# Cruzada_GPS_2015_rev1.net
KiCad netlist of a schematic drawn in EAGLE
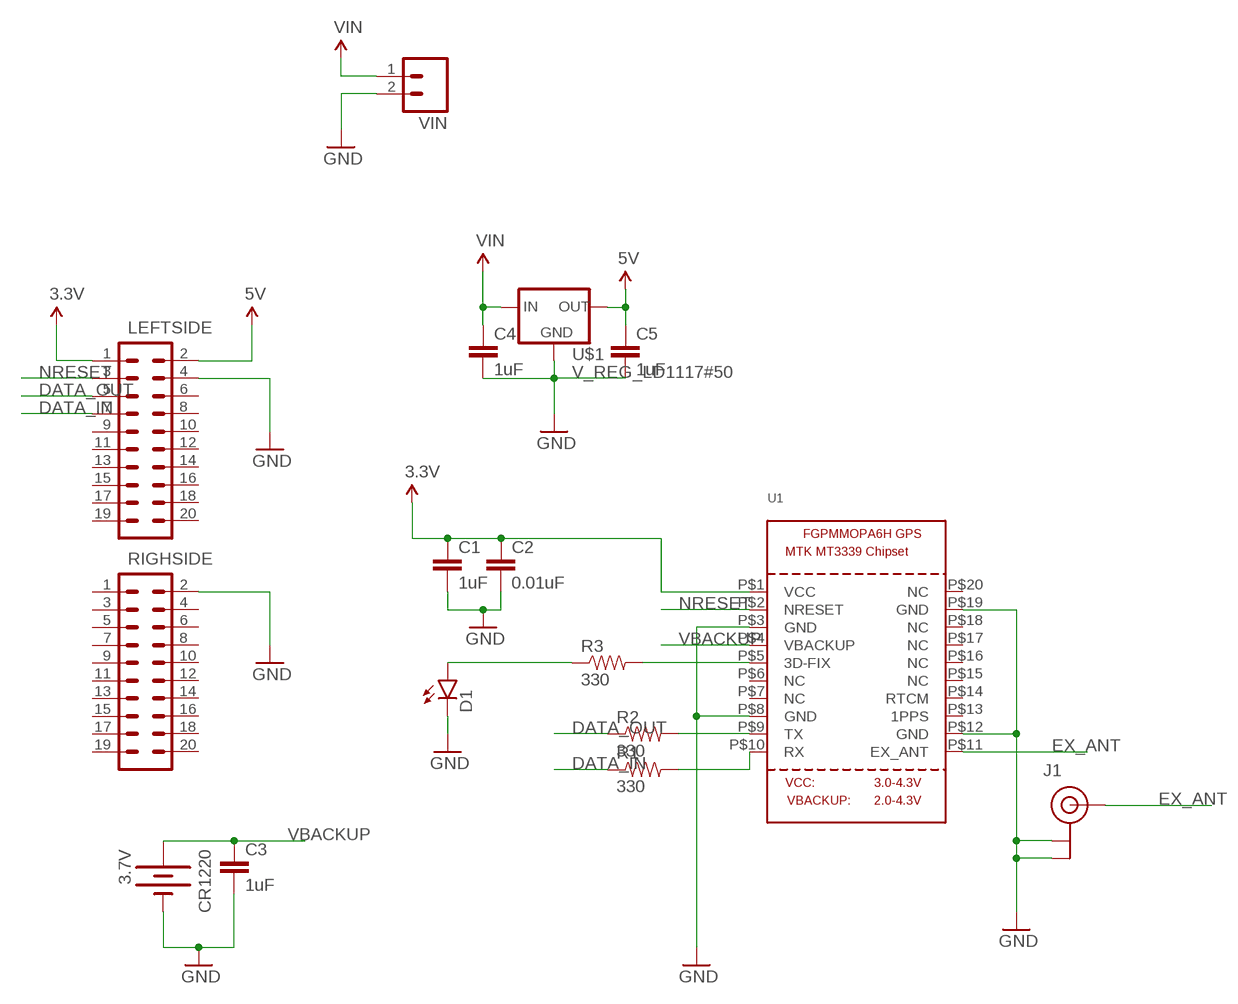
[diagram p0: schematic, sheet 1]

(export (version "E")
  (design (tool "Eeschema 10.0.6"))
  (components
    (comp (ref "C1")
      (value "1uF")
      (footprint "eagle-import:1206")
      (libsource (lib "eagle-import") (part "CAP1206"))
    )
    (comp (ref "C2")
      (value "0.01uF")
      (footprint "eagle-import:1206")
      (libsource (lib "eagle-import") (part "CAP1206"))
    )
    (comp (ref "C3")
      (value "1uF")
      (footprint "eagle-import:1206")
      (libsource (lib "eagle-import") (part "CAP1206"))
    )
    (comp (ref "C4")
      (value "1uF")
      (footprint "eagle-import:1206")
      (libsource (lib "eagle-import") (part "CAP1206"))
    )
    (comp (ref "C5")
      (value "1uF")
      (footprint "eagle-import:1206")
      (libsource (lib "eagle-import") (part "CAP1206"))
    )
    (comp (ref "CR1220")
      (value "3.7V")
      (footprint "eagle-import:BATTCON_12MM")
      (libsource (lib "eagle-import") (part "BATTERY12MM"))
    )
    (comp (ref "D1")
      (value "LED1206")
      (footprint "eagle-import:LED-1206")
      (libsource (lib "eagle-import") (part "LED1206"))
    )
    (comp (ref "J1")
      (value "U.FL")
      (footprint "eagle-import:U.FL")
      (libsource (lib "eagle-import") (part "U.FL"))
    )
    (comp (ref "LEFTSIDE")
      (value "M10X2")
      (footprint "eagle-import:2X10")
      (libsource (lib "eagle-import") (part "M10X2"))
    )
    (comp (ref "R1")
      (value "330")
      (footprint "eagle-import:1206")
      (libsource (lib "eagle-import") (part "RESISTOR1206"))
    )
    (comp (ref "R2")
      (value "330")
      (footprint "eagle-import:1206")
      (libsource (lib "eagle-import") (part "RESISTOR1206"))
    )
    (comp (ref "R3")
      (value "330")
      (footprint "eagle-import:1206")
      (libsource (lib "eagle-import") (part "RESISTOR1206"))
    )
    (comp (ref "RIGHSIDE")
      (value "M10X2")
      (footprint "eagle-import:2X10")
      (libsource (lib "eagle-import") (part "M10X2"))
    )
    (comp (ref "U$1")
      (value "V_REG_LD1117#50")
      (footprint "eagle-import:SOT223")
      (libsource (lib "eagle-import") (part "V_REG_MIC2920"))
    )
    (comp (ref "U1")
      (value "GPS_FGPMMOPA6H")
      (footprint "eagle-import:FGPMMOPA6H")
      (libsource (lib "eagle-import") (part "GPS_FGPMMOPA6H"))
    )
    (comp (ref "VIN")
      (value "M02PTH")
      (footprint "eagle-import:1X02")
      (libsource (lib "eagle-import") (part "M02PTH"))
    )
  )
  (nets
    (net (code "1") (name "/DATA_IN") (class "Default")
      (node (ref "LEFTSIDE") (pin "7") (pinfunction "7_7") (pintype "passive"))
      (node (ref "R1") (pin "1") (pinfunction "1_1") (pintype "passive"))
    )
    (net (code "2") (name "/DATA_OUT") (class "Default")
      (node (ref "LEFTSIDE") (pin "5") (pinfunction "5_5") (pintype "passive"))
      (node (ref "R2") (pin "1") (pinfunction "1_1") (pintype "passive"))
    )
    (net (code "3") (name "/EX_ANT") (class "Default")
      (node (ref "J1") (pin "P$3") (pinfunction "SIGNAL_P$3") (pintype "bidirectional"))
      (node (ref "U1") (pin "P$11") (pinfunction "EX_ANT_P$11") (pintype "bidirectional"))
    )
    (net (code "4") (name "/NRESET") (class "Default")
      (node (ref "LEFTSIDE") (pin "3") (pinfunction "3_3") (pintype "passive"))
      (node (ref "U1") (pin "P$2") (pinfunction "NRESET_P$2") (pintype "bidirectional"))
    )
    (net (code "5") (name "/VBACKUP") (class "Default")
      (node (ref "C3") (pin "1") (pinfunction "1_1") (pintype "passive"))
      (node (ref "CR1220") (pin "PWR@1") (pinfunction "+_PWR@1") (pintype "power_in"))
      (node (ref "U1") (pin "P$4") (pinfunction "VBACKUP_P$4") (pintype "bidirectional"))
    )
    (net (code "6") (name "3.3V") (class "Default")
      (node (ref "C1") (pin "1") (pinfunction "1_1") (pintype "passive"))
      (node (ref "C2") (pin "1") (pinfunction "1_1") (pintype "passive"))
      (node (ref "LEFTSIDE") (pin "1") (pinfunction "1_1") (pintype "passive"))
      (node (ref "U1") (pin "P$1") (pinfunction "VCC_P$1") (pintype "bidirectional"))
    )
    (net (code "7") (name "5V") (class "Default")
      (node (ref "C5") (pin "1") (pinfunction "1_1") (pintype "passive"))
      (node (ref "LEFTSIDE") (pin "2") (pinfunction "2_2") (pintype "passive"))
      (node (ref "U$1") (pin "3") (pinfunction "OUT_3") (pintype "output"))
    )
    (net (code "8") (name "GND") (class "Default")
      (node (ref "C1") (pin "2") (pinfunction "2_2") (pintype "passive"))
      (node (ref "C2") (pin "2") (pinfunction "2_2") (pintype "passive"))
      (node (ref "C3") (pin "2") (pinfunction "2_2") (pintype "passive"))
      (node (ref "C4") (pin "2") (pinfunction "2_2") (pintype "passive"))
      (node (ref "C5") (pin "2") (pinfunction "2_2") (pintype "passive"))
      (node (ref "CR1220") (pin "GND") (pinfunction "-_GND") (pintype "power_in"))
      (node (ref "D1") (pin "C") (pinfunction "C_C") (pintype "passive"))
      (node (ref "J1") (pin "P$1") (pinfunction "GND_P$1") (pintype "bidirectional"))
      (node (ref "J1") (pin "P$2") (pinfunction "GND_P$2") (pintype "bidirectional"))
      (node (ref "LEFTSIDE") (pin "4") (pinfunction "4_4") (pintype "passive"))
      (node (ref "RIGHSIDE") (pin "2") (pinfunction "2_2") (pintype "passive"))
      (node (ref "U$1") (pin "2") (pinfunction "GND_2") (pintype "input"))
      (node (ref "U1") (pin "P$12") (pinfunction "GND_P$12") (pintype "bidirectional"))
      (node (ref "U1") (pin "P$19") (pinfunction "GND_P$19") (pintype "bidirectional"))
      (node (ref "U1") (pin "P$3") (pinfunction "GND_P$3") (pintype "bidirectional"))
      (node (ref "U1") (pin "P$8") (pinfunction "GND_P$8") (pintype "bidirectional"))
      (node (ref "VIN") (pin "2") (pinfunction "2_2") (pintype "passive"))
    )
    (net (code "9") (name "Net-(D1-PadA)") (class "Default")
      (node (ref "D1") (pin "A") (pinfunction "A_A") (pintype "passive"))
      (node (ref "R3") (pin "1") (pinfunction "1_1") (pintype "passive"))
    )
    (net (code "10") (name "Net-(U1-3D-FIX)") (class "Default")
      (node (ref "R3") (pin "2") (pinfunction "2_2") (pintype "passive"))
      (node (ref "U1") (pin "P$5") (pinfunction "3D-FIX_P$5") (pintype "bidirectional"))
    )
    (net (code "11") (name "Net-(U1-RX)") (class "Default")
      (node (ref "R1") (pin "2") (pinfunction "2_2") (pintype "passive"))
      (node (ref "U1") (pin "P$10") (pinfunction "RX_P$10") (pintype "bidirectional"))
    )
    (net (code "12") (name "Net-(U1-TX)") (class "Default")
      (node (ref "R2") (pin "2") (pinfunction "2_2") (pintype "passive"))
      (node (ref "U1") (pin "P$9") (pinfunction "TX_P$9") (pintype "bidirectional"))
    )
    (net (code "13") (name "VIN") (class "Default")
      (node (ref "C4") (pin "1") (pinfunction "1_1") (pintype "passive"))
      (node (ref "U$1") (pin "1") (pinfunction "IN_1") (pintype "input"))
      (node (ref "VIN") (pin "1") (pinfunction "1_1") (pintype "passive"))
    )
    (net (code "14") (name "unconnected-(LEFTSIDE-Pad6)") (class "Default")
      (node (ref "LEFTSIDE") (pin "6") (pinfunction "6_6") (pintype "passive"))
    )
    (net (code "15") (name "unconnected-(LEFTSIDE-Pad8)") (class "Default")
      (node (ref "LEFTSIDE") (pin "8") (pinfunction "8_8") (pintype "passive"))
    )
    (net (code "16") (name "unconnected-(LEFTSIDE-Pad9)") (class "Default")
      (node (ref "LEFTSIDE") (pin "9") (pinfunction "9_9") (pintype "passive"))
    )
    (net (code "17") (name "unconnected-(LEFTSIDE-Pad10)") (class "Default")
      (node (ref "LEFTSIDE") (pin "10") (pinfunction "10_10") (pintype "passive"))
    )
    (net (code "18") (name "unconnected-(LEFTSIDE-Pad11)") (class "Default")
      (node (ref "LEFTSIDE") (pin "11") (pinfunction "11_11") (pintype "passive"))
    )
    (net (code "19") (name "unconnected-(LEFTSIDE-Pad12)") (class "Default")
      (node (ref "LEFTSIDE") (pin "12") (pinfunction "12_12") (pintype "passive"))
    )
    (net (code "20") (name "unconnected-(LEFTSIDE-Pad13)") (class "Default")
      (node (ref "LEFTSIDE") (pin "13") (pinfunction "13_13") (pintype "passive"))
    )
    (net (code "21") (name "unconnected-(LEFTSIDE-Pad14)") (class "Default")
      (node (ref "LEFTSIDE") (pin "14") (pinfunction "14_14") (pintype "passive"))
    )
    (net (code "22") (name "unconnected-(LEFTSIDE-Pad15)") (class "Default")
      (node (ref "LEFTSIDE") (pin "15") (pinfunction "15_15") (pintype "passive"))
    )
    (net (code "23") (name "unconnected-(LEFTSIDE-Pad16)") (class "Default")
      (node (ref "LEFTSIDE") (pin "16") (pinfunction "16_16") (pintype "passive"))
    )
    (net (code "24") (name "unconnected-(LEFTSIDE-Pad17)") (class "Default")
      (node (ref "LEFTSIDE") (pin "17") (pinfunction "17_17") (pintype "passive"))
    )
    (net (code "25") (name "unconnected-(LEFTSIDE-Pad18)") (class "Default")
      (node (ref "LEFTSIDE") (pin "18") (pinfunction "18_18") (pintype "passive"))
    )
    (net (code "26") (name "unconnected-(LEFTSIDE-Pad19)") (class "Default")
      (node (ref "LEFTSIDE") (pin "19") (pinfunction "19_19") (pintype "passive"))
    )
    (net (code "27") (name "unconnected-(LEFTSIDE-Pad20)") (class "Default")
      (node (ref "LEFTSIDE") (pin "20") (pinfunction "20_20") (pintype "passive"))
    )
    (net (code "28") (name "unconnected-(RIGHSIDE-Pad1)") (class "Default")
      (node (ref "RIGHSIDE") (pin "1") (pinfunction "1_1") (pintype "passive"))
    )
    (net (code "29") (name "unconnected-(RIGHSIDE-Pad3)") (class "Default")
      (node (ref "RIGHSIDE") (pin "3") (pinfunction "3_3") (pintype "passive"))
    )
    (net (code "30") (name "unconnected-(RIGHSIDE-Pad4)") (class "Default")
      (node (ref "RIGHSIDE") (pin "4") (pinfunction "4_4") (pintype "passive"))
    )
    (net (code "31") (name "unconnected-(RIGHSIDE-Pad5)") (class "Default")
      (node (ref "RIGHSIDE") (pin "5") (pinfunction "5_5") (pintype "passive"))
    )
    (net (code "32") (name "unconnected-(RIGHSIDE-Pad6)") (class "Default")
      (node (ref "RIGHSIDE") (pin "6") (pinfunction "6_6") (pintype "passive"))
    )
    (net (code "33") (name "unconnected-(RIGHSIDE-Pad7)") (class "Default")
      (node (ref "RIGHSIDE") (pin "7") (pinfunction "7_7") (pintype "passive"))
    )
    (net (code "34") (name "unconnected-(RIGHSIDE-Pad8)") (class "Default")
      (node (ref "RIGHSIDE") (pin "8") (pinfunction "8_8") (pintype "passive"))
    )
    (net (code "35") (name "unconnected-(RIGHSIDE-Pad9)") (class "Default")
      (node (ref "RIGHSIDE") (pin "9") (pinfunction "9_9") (pintype "passive"))
    )
    (net (code "36") (name "unconnected-(RIGHSIDE-Pad10)") (class "Default")
      (node (ref "RIGHSIDE") (pin "10") (pinfunction "10_10") (pintype "passive"))
    )
    (net (code "37") (name "unconnected-(RIGHSIDE-Pad11)") (class "Default")
      (node (ref "RIGHSIDE") (pin "11") (pinfunction "11_11") (pintype "passive"))
    )
    (net (code "38") (name "unconnected-(RIGHSIDE-Pad12)") (class "Default")
      (node (ref "RIGHSIDE") (pin "12") (pinfunction "12_12") (pintype "passive"))
    )
    (net (code "39") (name "unconnected-(RIGHSIDE-Pad13)") (class "Default")
      (node (ref "RIGHSIDE") (pin "13") (pinfunction "13_13") (pintype "passive"))
    )
    (net (code "40") (name "unconnected-(RIGHSIDE-Pad14)") (class "Default")
      (node (ref "RIGHSIDE") (pin "14") (pinfunction "14_14") (pintype "passive"))
    )
    (net (code "41") (name "unconnected-(RIGHSIDE-Pad15)") (class "Default")
      (node (ref "RIGHSIDE") (pin "15") (pinfunction "15_15") (pintype "passive"))
    )
    (net (code "42") (name "unconnected-(RIGHSIDE-Pad16)") (class "Default")
      (node (ref "RIGHSIDE") (pin "16") (pinfunction "16_16") (pintype "passive"))
    )
    (net (code "43") (name "unconnected-(RIGHSIDE-Pad17)") (class "Default")
      (node (ref "RIGHSIDE") (pin "17") (pinfunction "17_17") (pintype "passive"))
    )
    (net (code "44") (name "unconnected-(RIGHSIDE-Pad18)") (class "Default")
      (node (ref "RIGHSIDE") (pin "18") (pinfunction "18_18") (pintype "passive"))
    )
    (net (code "45") (name "unconnected-(RIGHSIDE-Pad19)") (class "Default")
      (node (ref "RIGHSIDE") (pin "19") (pinfunction "19_19") (pintype "passive"))
    )
    (net (code "46") (name "unconnected-(RIGHSIDE-Pad20)") (class "Default")
      (node (ref "RIGHSIDE") (pin "20") (pinfunction "20_20") (pintype "passive"))
    )
    (net (code "47") (name "unconnected-(U1-1PPS-PadP$13)") (class "Default")
      (node (ref "U1") (pin "P$13") (pinfunction "1PPS_P$13") (pintype "bidirectional"))
    )
    (net (code "48") (name "unconnected-(U1-NC-PadP$6)") (class "Default")
      (node (ref "U1") (pin "P$6") (pinfunction "NC_P$6") (pintype "bidirectional"))
    )
    (net (code "49") (name "unconnected-(U1-NC-PadP$7)") (class "Default")
      (node (ref "U1") (pin "P$7") (pinfunction "NC_P$7") (pintype "bidirectional"))
    )
    (net (code "50") (name "unconnected-(U1-NC-PadP$15)") (class "Default")
      (node (ref "U1") (pin "P$15") (pinfunction "NC_P$15") (pintype "bidirectional"))
    )
    (net (code "51") (name "unconnected-(U1-NC-PadP$16)") (class "Default")
      (node (ref "U1") (pin "P$16") (pinfunction "NC_P$16") (pintype "bidirectional"))
    )
    (net (code "52") (name "unconnected-(U1-NC-PadP$17)") (class "Default")
      (node (ref "U1") (pin "P$17") (pinfunction "NC_P$17") (pintype "bidirectional"))
    )
    (net (code "53") (name "unconnected-(U1-NC-PadP$18)") (class "Default")
      (node (ref "U1") (pin "P$18") (pinfunction "NC_P$18") (pintype "bidirectional"))
    )
    (net (code "54") (name "unconnected-(U1-NC-PadP$20)") (class "Default")
      (node (ref "U1") (pin "P$20") (pinfunction "NC_P$20") (pintype "bidirectional"))
    )
    (net (code "55") (name "unconnected-(U1-RTCM-PadP$14)") (class "Default")
      (node (ref "U1") (pin "P$14") (pinfunction "RTCM_P$14") (pintype "bidirectional"))
    )
  )
)
